# Power.net
KiCad netlist of a schematic drawn in Altium Designer
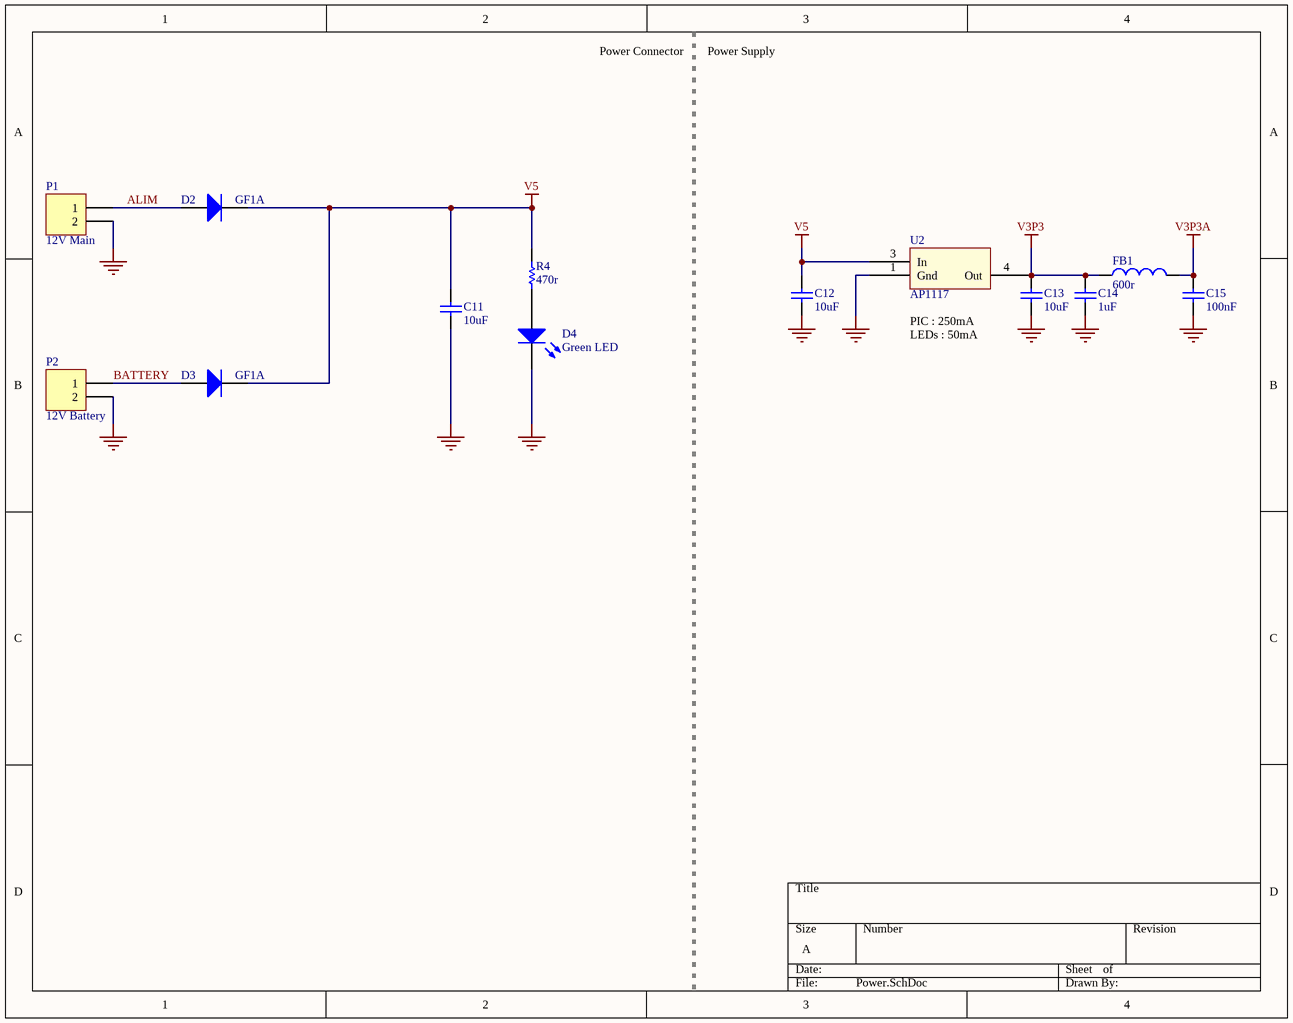
[diagram p0: Power.SchDoc]

(export (version "E")
  (design (tool "Eeschema 10.0.6"))
  (components
    (comp (ref "C11")
      (value "10uF")
      (footprint "CAPC2012N")
      (description "Capacitor")
      (libsource (lib "Miscellaneous Devices") (part "Cap"))
    )
    (comp (ref "C12")
      (value "10uF")
      (footprint "CAPC2012N")
      (description "Capacitor")
      (libsource (lib "Miscellaneous Devices") (part "Cap"))
    )
    (comp (ref "C13")
      (value "10uF")
      (footprint "CAPC2012N")
      (description "Capacitor")
      (libsource (lib "Miscellaneous Devices") (part "Cap"))
    )
    (comp (ref "C14")
      (value "1uF")
      (footprint "CAPC1608N")
      (description "Capacitor")
      (libsource (lib "Miscellaneous Devices") (part "Cap"))
    )
    (comp (ref "C15")
      (value "100nF")
      (footprint "CAPC1608N")
      (description "Capacitor")
      (libsource (lib "Miscellaneous Devices") (part "Cap"))
    )
    (comp (ref "D2")
      (value "GF1A")
      (footprint "214AC_21")
      (description "Default Diode")
      (libsource (lib "Miscellaneous Devices") (part "Diode"))
    )
    (comp (ref "D3")
      (value "GF1A")
      (footprint "214AC_21")
      (description "Default Diode")
      (libsource (lib "Miscellaneous Devices") (part "Diode"))
    )
    (comp (ref "D4")
      (value "Green LED")
      (footprint "LED 0805")
      (description "Typical INFRARED GaAs LED")
      (libsource (lib "Miscellaneous Devices") (part "LED0"))
    )
    (comp (ref "FB1")
      (value "600r")
      (footprint "INDC1608AN")
      (description "Inductor")
      (libsource (lib "Miscellaneous Devices") (part "Inductor"))
    )
    (comp (ref "P1")
      (value "12V Main")
      (footprint "PHOENIX_1985195")
      (description "Header, 2-Pin")
      (libsource (lib "Miscellaneous Connectors") (part "Header 2"))
    )
    (comp (ref "P2")
      (value "12V Battery")
      (footprint "PHOENIX_1985195")
      (description "Header, 2-Pin")
      (libsource (lib "Miscellaneous Connectors") (part "Header 2"))
    )
    (comp (ref "R4")
      (value "470r")
      (footprint "RESC1608N")
      (description "Resistor")
      (libsource (lib "Miscellaneous Devices") (part "Res1"))
    )
    (comp (ref "U2") (value "AP1117") (footprint "TD03B_N") (libsource (lib "Schlib1") (part "AP1117")))
  )
  (nets
    (net (code "1") (name "/ALIM") (class "Default")
      (node (ref "D2") (pin "1") (pinfunction "A_1") (pintype "passive"))
      (node (ref "P1") (pin "1") (pinfunction "1_1") (pintype "passive"))
    )
    (net (code "2") (name "/BATTERY") (class "Default")
      (node (ref "D3") (pin "1") (pinfunction "A_1") (pintype "passive"))
      (node (ref "P2") (pin "1") (pinfunction "1_1") (pintype "passive"))
    )
    (net (code "3") (name "GND") (class "Default")
      (node (ref "C11") (pin "1") (pinfunction "1_1") (pintype "passive"))
      (node (ref "C12") (pin "1") (pinfunction "1_1") (pintype "passive"))
      (node (ref "C13") (pin "1") (pinfunction "1_1") (pintype "passive"))
      (node (ref "C14") (pin "1") (pinfunction "1_1") (pintype "passive"))
      (node (ref "C15") (pin "1") (pinfunction "1_1") (pintype "passive"))
      (node (ref "D4") (pin "2") (pinfunction "K_2") (pintype "passive"))
      (node (ref "P1") (pin "2") (pinfunction "2_2") (pintype "passive"))
      (node (ref "P2") (pin "2") (pinfunction "2_2") (pintype "passive"))
      (node (ref "U2") (pin "1") (pinfunction "Gnd_1") (pintype "passive"))
    )
    (net (code "4") (name "Net-(D4-A)") (class "Default")
      (node (ref "D4") (pin "1") (pinfunction "A_1") (pintype "passive"))
      (node (ref "R4") (pin "1") (pinfunction "1_1") (pintype "passive"))
    )
    (net (code "5") (name "V3P3") (class "Default")
      (node (ref "C13") (pin "2") (pinfunction "2_2") (pintype "passive"))
      (node (ref "C14") (pin "2") (pinfunction "2_2") (pintype "passive"))
      (node (ref "FB1") (pin "1") (pinfunction "1_1") (pintype "passive"))
      (node (ref "U2") (pin "4") (pinfunction "Out_4") (pintype "passive"))
    )
    (net (code "6") (name "V3P3A") (class "Default")
      (node (ref "C15") (pin "2") (pinfunction "2_2") (pintype "passive"))
      (node (ref "FB1") (pin "2") (pinfunction "2_2") (pintype "passive"))
    )
    (net (code "7") (name "V5") (class "Default")
      (node (ref "C11") (pin "2") (pinfunction "2_2") (pintype "passive"))
      (node (ref "C12") (pin "2") (pinfunction "2_2") (pintype "passive"))
      (node (ref "D2") (pin "2") (pinfunction "K_2") (pintype "passive"))
      (node (ref "D3") (pin "2") (pinfunction "K_2") (pintype "passive"))
      (node (ref "R4") (pin "2") (pinfunction "2_2") (pintype "passive"))
      (node (ref "U2") (pin "3") (pinfunction "In_3") (pintype "passive"))
    )
  )
)
